# SCH_cool_thing_2025-05-27.net
KiCad netlist of a schematic drawn in EasyEDA
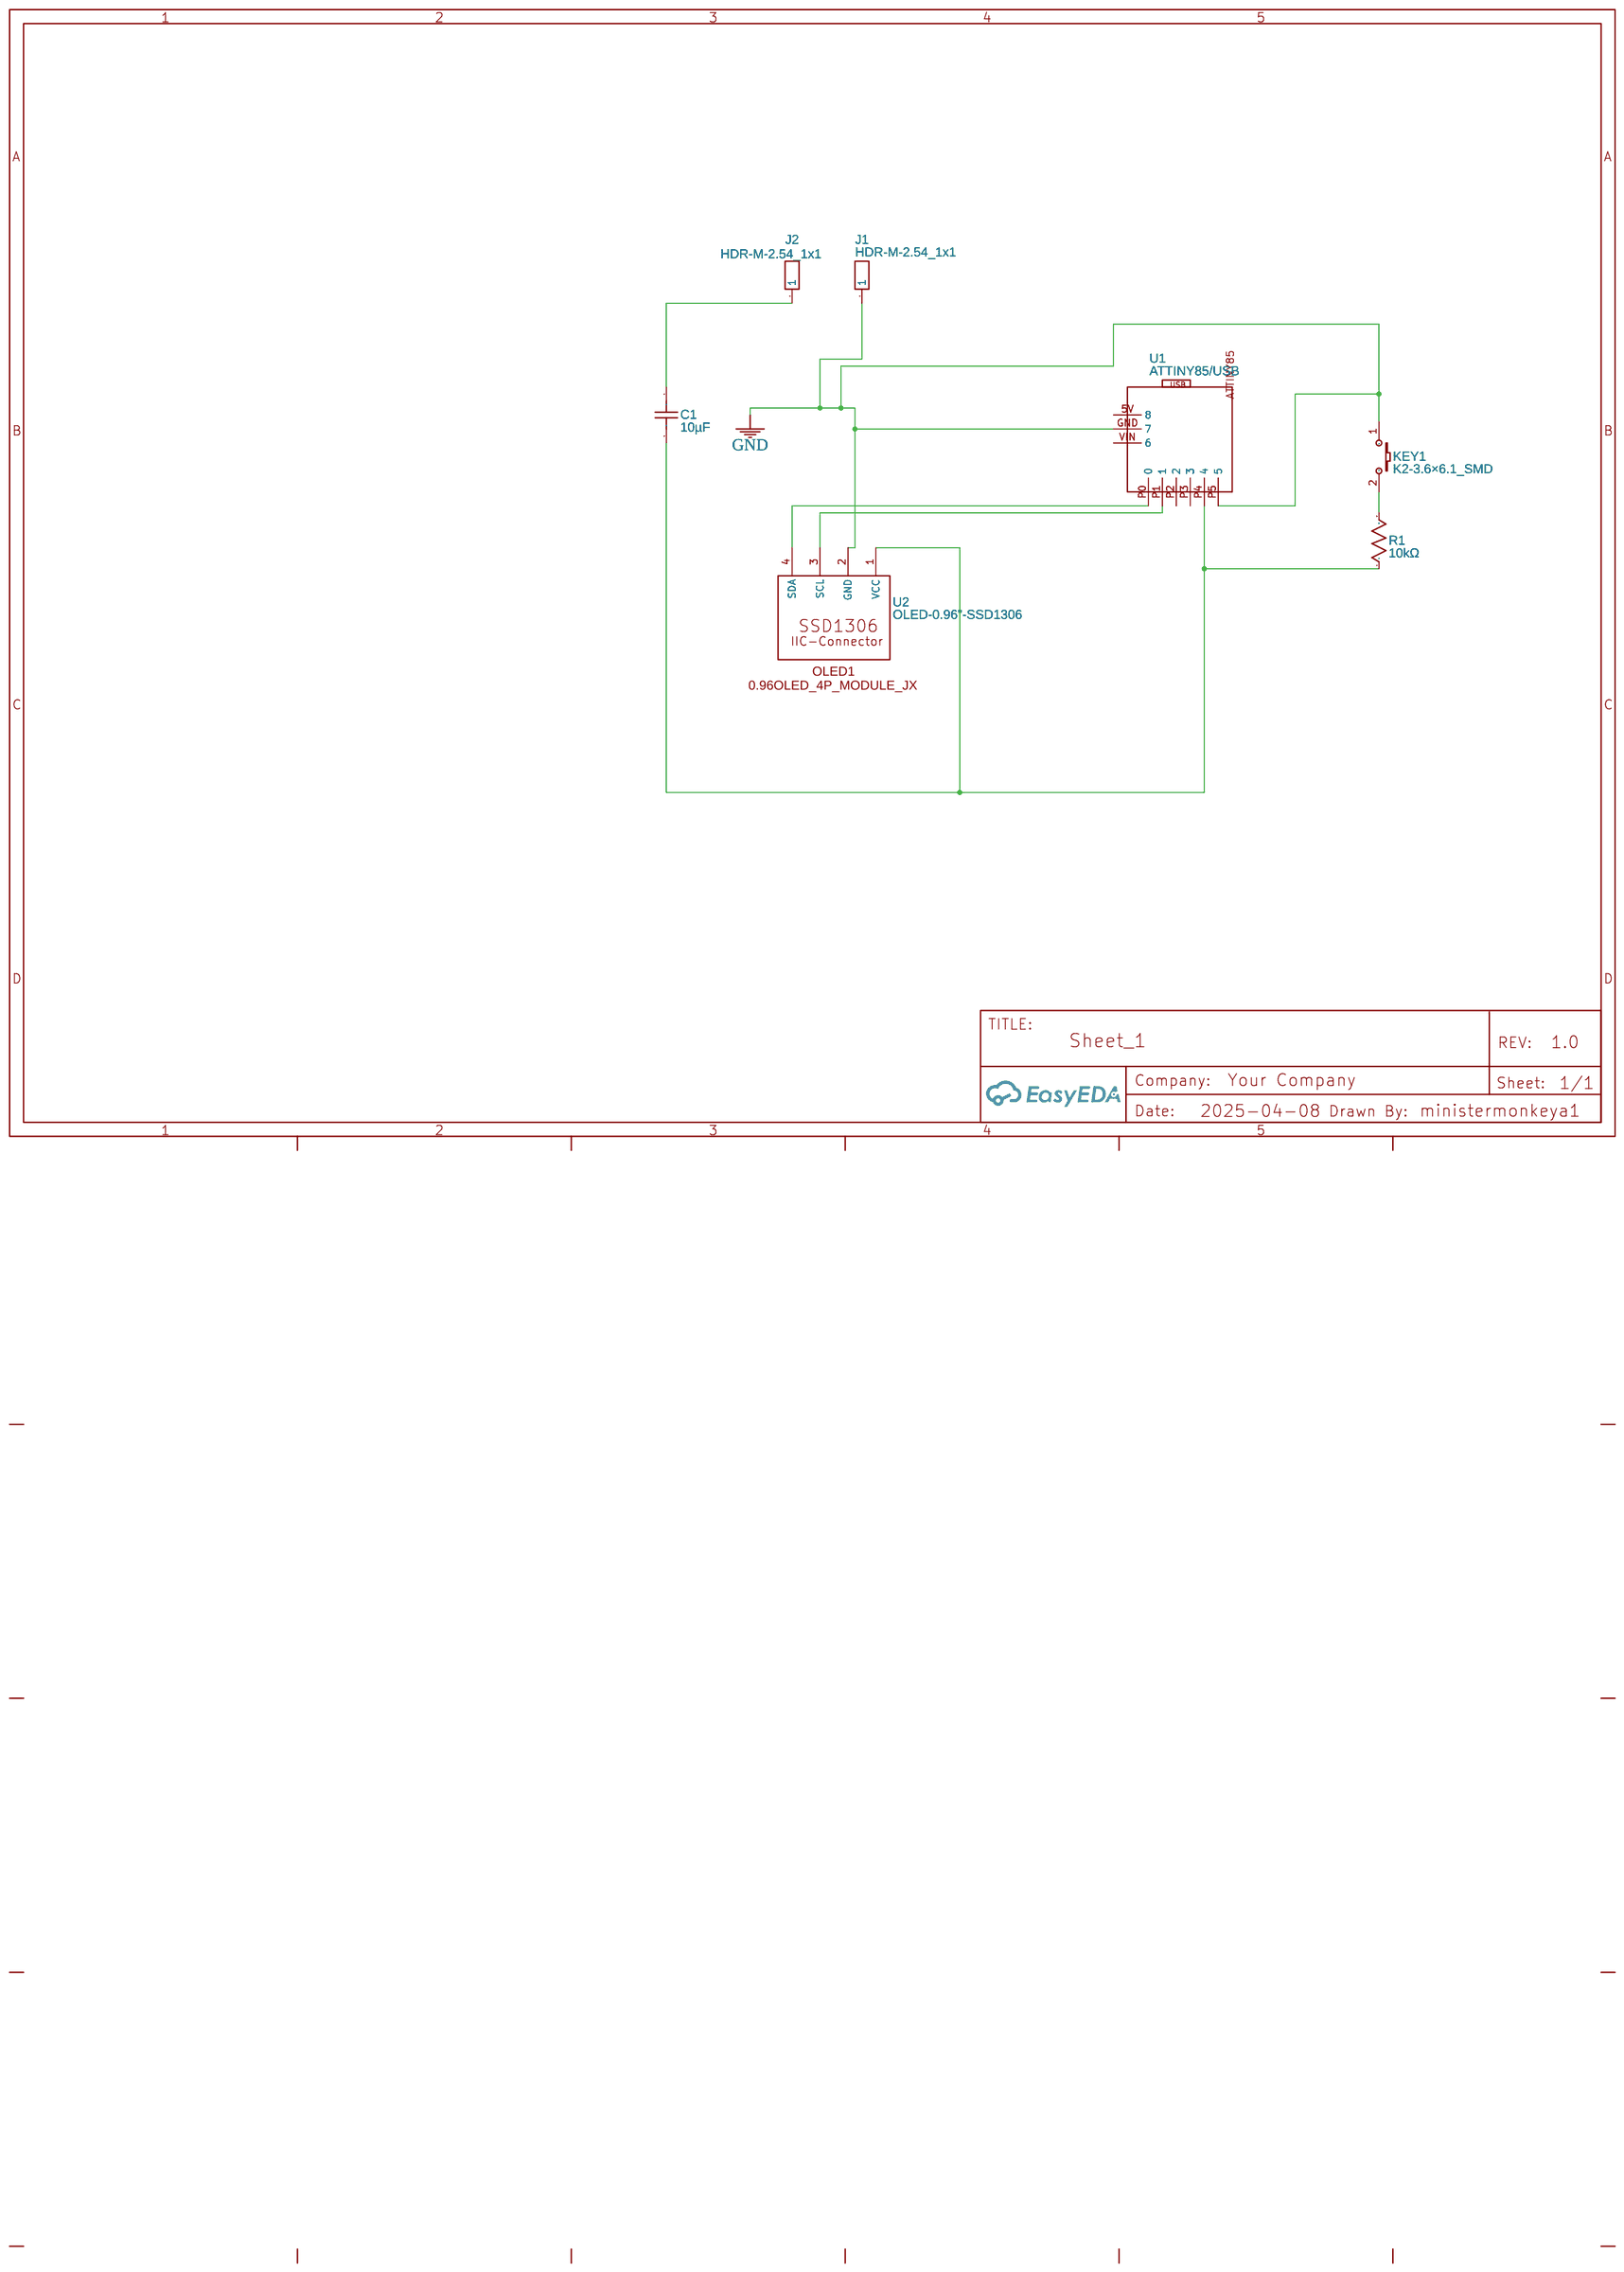
[diagram p0: schematic sheet]

(export (version "E")
  (design (tool "Eeschema 10.0.6"))
  (components
    (comp (ref "C1") (value "10µF") (libsource (lib "") (part "C_0603_US")))
    (comp (ref "J1") (value "HDR-M-2.54_1x1") (libsource (lib "") (part "HDR-M-2.54_1x1")))
    (comp (ref "J2") (value "HDR-M-2.54_1x1") (libsource (lib "") (part "HDR-M-2.54_1x1")))
    (comp (ref "KEY1")
      (value "K2-3.6×6.1_SMD")
      (fields (field (name "Manufacturer Part") "K2-1107ST-A4SW-06"))
      (libsource (lib "") (part "K2-3.6×6.1_SMD"))
    )
    (comp (ref "R1") (value "10kΩ") (libsource (lib "") (part "R_0603_US")))
    (comp (ref "U1") (value "ATTINY85/USB") (libsource (lib "") (part "ATTINY85/USB")))
    (comp (ref "U2") (value "OLED-0.96\"-SSD1306") (libsource (lib "") (part "OLED-0.96{dblquote}-SSD1306")))
  )
  (nets
    (net (code "1") (name "GND") (class "Default")
      (node (ref "J1") (pin "1") (pinfunction "1_1") (pintype "input"))
      (node (ref "KEY1") (pin "1") (pinfunction "1_1") (pintype "unspecified"))
      (node (ref "U1") (pin "GND") (pinfunction "7_GND") (pintype "unspecified"))
      (node (ref "U1") (pin "P5") (pinfunction "5_P5") (pintype "unspecified"))
      (node (ref "U2") (pin "2") (pinfunction "GND_2") (pintype "unspecified"))
    )
    (net (code "2") (name "Net-(C1-Pad1)") (class "Default")
      (node (ref "C1") (pin "1") (pinfunction "1_1") (pintype "unspecified"))
      (node (ref "J2") (pin "1") (pinfunction "1_1") (pintype "input"))
    )
    (net (code "3") (name "Net-(KEY1-Pad2)") (class "Default")
      (node (ref "KEY1") (pin "2") (pinfunction "2_2") (pintype "unspecified"))
      (node (ref "R1") (pin "2") (pinfunction "2_2") (pintype "unspecified"))
    )
    (net (code "4") (name "Net-(U1-0)") (class "Default")
      (node (ref "U1") (pin "P0") (pinfunction "0_P0") (pintype "unspecified"))
      (node (ref "U2") (pin "4") (pinfunction "SDA_4") (pintype "unspecified"))
    )
    (net (code "5") (name "Net-(U1-1)") (class "Default")
      (node (ref "U1") (pin "P1") (pinfunction "1_P1") (pintype "unspecified"))
      (node (ref "U2") (pin "3") (pinfunction "SCL_3") (pintype "unspecified"))
    )
    (net (code "6") (name "Net-(U1-4)") (class "Default")
      (node (ref "C1") (pin "2") (pinfunction "2_2") (pintype "unspecified"))
      (node (ref "R1") (pin "1") (pinfunction "1_1") (pintype "unspecified"))
      (node (ref "U1") (pin "P4") (pinfunction "4_P4") (pintype "unspecified"))
      (node (ref "U2") (pin "1") (pinfunction "VCC_1") (pintype "unspecified"))
    )
    (net (code "7") (name "unconnected-(U1-2-PadP2)") (class "Default")
      (node (ref "U1") (pin "P2") (pinfunction "2_P2") (pintype "unspecified"))
    )
    (net (code "8") (name "unconnected-(U1-3-PadP3)") (class "Default")
      (node (ref "U1") (pin "P3") (pinfunction "3_P3") (pintype "unspecified"))
    )
    (net (code "9") (name "unconnected-(U1-6-PadVIN)") (class "Default")
      (node (ref "U1") (pin "VIN") (pinfunction "6_VIN") (pintype "unspecified"))
    )
    (net (code "10") (name "unconnected-(U1-8-Pad5V)") (class "Default")
      (node (ref "U1") (pin "5V") (pinfunction "8_5V") (pintype "unspecified"))
    )
  )
)
